# shield_passage_vitesse.net
KiCad netlist of a schematic drawn in EAGLE
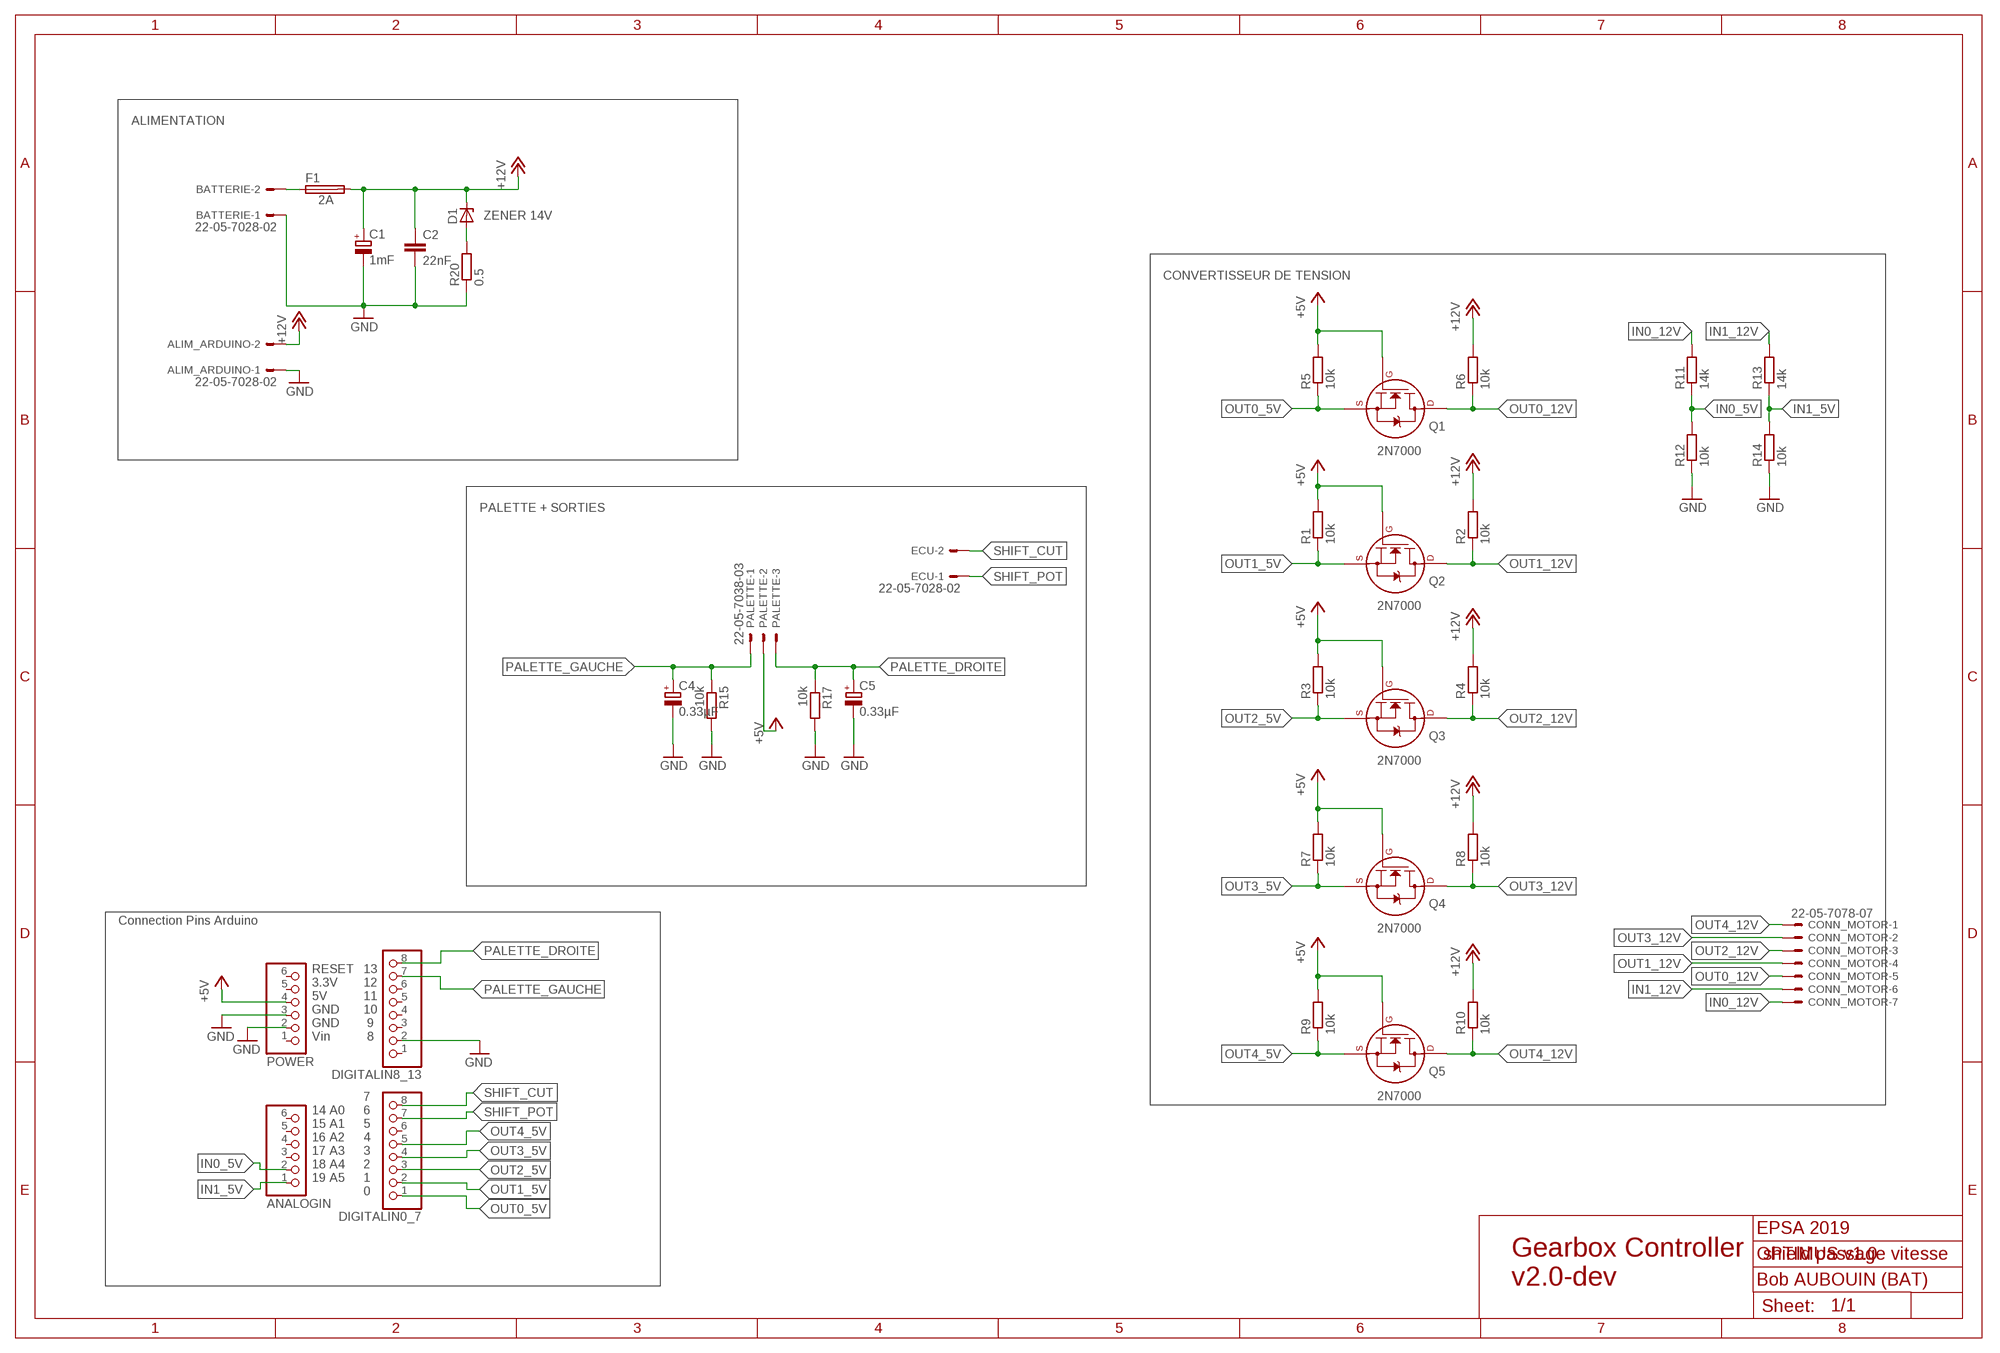
[diagram p0: schematic, sheet 1]

(export (version "E")
  (design (tool "Eeschema 10.0.6"))
  (components
    (comp (ref "ALIM_ARDUINO")
      (value "22-05-7028-02")
      (footprint "eagle-import:7395-02")
      (libsource (lib "eagle-import") (part "22-?-0205-7028"))
    )
    (comp (ref "ANALOGIN")
      (value "PINHD-1X6CB")
      (footprint "eagle-import:1X06-CLEANBIG")
      (libsource (lib "eagle-import") (part "PINHD-1X6CB"))
    )
    (comp (ref "BATTERIE")
      (value "22-05-7028-02")
      (footprint "eagle-import:7395-02")
      (libsource (lib "eagle-import") (part "22-?-0205-7028"))
    )
    (comp (ref "C1")
      (value "1mF")
      (footprint "eagle-import:E7,5-16")
      (libsource (lib "eagle-import") (part "rcl_334_CPOL-EUE7.5-16"))
    )
    (comp (ref "C2")
      (value "22nF")
      (footprint "eagle-import:C025-025X050")
      (libsource (lib "eagle-import") (part "C-EU025-025X050"))
    )
    (comp (ref "C4")
      (value "0.33µF")
      (footprint "eagle-import:E2,5-6E")
      (libsource (lib "eagle-import") (part "CPOL-EUE2,5-6E"))
    )
    (comp (ref "C5")
      (value "0.33µF")
      (footprint "eagle-import:E2,5-6E")
      (libsource (lib "eagle-import") (part "CPOL-EUE2,5-6E"))
    )
    (comp (ref "CONN_MOTOR")
      (value "22-05-7078-07")
      (footprint "eagle-import:7395-07")
      (libsource (lib "eagle-import") (part "22-?-0705-7078"))
    )
    (comp (ref "D1")
      (value "ZENER 14V")
      (footprint "eagle-import:DO41Z10")
      (libsource (lib "eagle-import") (part "ZENER-DIODEDO41Z10"))
    )
    (comp (ref "DIGITALIN0_7")
      (value "PINHD-1X8CLEANBIG")
      (footprint "eagle-import:1X08-CLEANBIG")
      (libsource (lib "eagle-import") (part "PINHD-1X8CLEANBIG"))
    )
    (comp (ref "DIGITALIN8_13")
      (value "PINHD-1X8CLEANBIG")
      (footprint "eagle-import:1X08-CLEANBIG")
      (libsource (lib "eagle-import") (part "PINHD-1X8CLEANBIG"))
    )
    (comp (ref "ECU")
      (value "22-05-7028-02")
      (footprint "eagle-import:7395-02")
      (libsource (lib "eagle-import") (part "22-?-0205-7028"))
    )
    (comp (ref "F1")
      (value "2A")
      (footprint "eagle-import:SH25")
      (fields (field (name "MF") "SCHURTER") (field (name "MPN") "0031.8211"))
      (libsource (lib "eagle-import") (part "SH25"))
    )
    (comp (ref "PALETTE")
      (value "22-05-7038-03")
      (footprint "eagle-import:7395-03")
      (libsource (lib "eagle-import") (part "22-?-0305-7038"))
    )
    (comp (ref "POWER")
      (value "PINHD-1X6CB")
      (footprint "eagle-import:1X06-CLEANBIG")
      (libsource (lib "eagle-import") (part "PINHD-1X6CB"))
    )
    (comp (ref "Q1")
      (value "2N7000")
      (footprint "eagle-import:TO-92")
      (libsource (lib "eagle-import") (part "2N700_TO920"))
    )
    (comp (ref "Q2")
      (value "2N7000")
      (footprint "eagle-import:TO-92")
      (libsource (lib "eagle-import") (part "2N700_TO920"))
    )
    (comp (ref "Q3")
      (value "2N7000")
      (footprint "eagle-import:TO-92")
      (libsource (lib "eagle-import") (part "2N700_TO920"))
    )
    (comp (ref "Q4")
      (value "2N7000")
      (footprint "eagle-import:TO-92")
      (libsource (lib "eagle-import") (part "2N700_TO920"))
    )
    (comp (ref "Q5")
      (value "2N7000")
      (footprint "eagle-import:TO-92")
      (libsource (lib "eagle-import") (part "2N700_TO920"))
    )
    (comp (ref "R1")
      (value "10k")
      (footprint "eagle-import:0204_7")
      (libsource (lib "eagle-import") (part "R-EU_0204/7"))
    )
    (comp (ref "R2")
      (value "10k")
      (footprint "eagle-import:0204_7")
      (libsource (lib "eagle-import") (part "R-EU_0204/7"))
    )
    (comp (ref "R3")
      (value "10k")
      (footprint "eagle-import:0204_7")
      (libsource (lib "eagle-import") (part "R-EU_0204/7"))
    )
    (comp (ref "R4")
      (value "10k")
      (footprint "eagle-import:0204_7")
      (libsource (lib "eagle-import") (part "R-EU_0204/7"))
    )
    (comp (ref "R5")
      (value "10k")
      (footprint "eagle-import:0204_7")
      (libsource (lib "eagle-import") (part "R-EU_0204/7"))
    )
    (comp (ref "R6")
      (value "10k")
      (footprint "eagle-import:0204_7")
      (libsource (lib "eagle-import") (part "R-EU_0204/7"))
    )
    (comp (ref "R7")
      (value "10k")
      (footprint "eagle-import:0204_7")
      (libsource (lib "eagle-import") (part "R-EU_0204/7"))
    )
    (comp (ref "R8")
      (value "10k")
      (footprint "eagle-import:0204_7")
      (libsource (lib "eagle-import") (part "R-EU_0204/7"))
    )
    (comp (ref "R9")
      (value "10k")
      (footprint "eagle-import:0204_7")
      (libsource (lib "eagle-import") (part "R-EU_0204/7"))
    )
    (comp (ref "R10")
      (value "10k")
      (footprint "eagle-import:0204_7")
      (libsource (lib "eagle-import") (part "R-EU_0204/7"))
    )
    (comp (ref "R11")
      (value "14k")
      (footprint "eagle-import:0204_7")
      (libsource (lib "eagle-import") (part "R-EU_0204/7"))
    )
    (comp (ref "R12")
      (value "10k")
      (footprint "eagle-import:0204_7")
      (libsource (lib "eagle-import") (part "R-EU_0204/7"))
    )
    (comp (ref "R13")
      (value "14k")
      (footprint "eagle-import:0204_7")
      (libsource (lib "eagle-import") (part "R-EU_0204/7"))
    )
    (comp (ref "R14")
      (value "10k")
      (footprint "eagle-import:0204_7")
      (libsource (lib "eagle-import") (part "R-EU_0204/7"))
    )
    (comp (ref "R15")
      (value "10k")
      (footprint "eagle-import:0204_7")
      (libsource (lib "eagle-import") (part "R-EU_0204/7"))
    )
    (comp (ref "R17")
      (value "10k")
      (footprint "eagle-import:0204_7")
      (libsource (lib "eagle-import") (part "R-EU_0204/7"))
    )
    (comp (ref "R20")
      (value "0.5")
      (footprint "eagle-import:0309_12")
      (libsource (lib "eagle-import") (part "R-EU_0309/12"))
    )
  )
  (nets
    (net (code "1") (name "+5V") (class "Default")
      (node (ref "PALETTE") (pin "2") (pinfunction "S_2") (pintype "passive"))
      (node (ref "POWER") (pin "4") (pinfunction "4_4") (pintype "passive"))
      (node (ref "Q1") (pin "2") (pinfunction "G_2") (pintype "tri_state"))
      (node (ref "Q2") (pin "2") (pinfunction "G_2") (pintype "tri_state"))
      (node (ref "Q3") (pin "2") (pinfunction "G_2") (pintype "tri_state"))
      (node (ref "Q4") (pin "2") (pinfunction "G_2") (pintype "tri_state"))
      (node (ref "Q5") (pin "2") (pinfunction "G_2") (pintype "tri_state"))
      (node (ref "R1") (pin "2") (pinfunction "2_2") (pintype "passive"))
      (node (ref "R3") (pin "2") (pinfunction "2_2") (pintype "passive"))
      (node (ref "R5") (pin "2") (pinfunction "2_2") (pintype "passive"))
      (node (ref "R7") (pin "2") (pinfunction "2_2") (pintype "passive"))
      (node (ref "R9") (pin "2") (pinfunction "2_2") (pintype "passive"))
    )
    (net (code "2") (name "+12V") (class "Default")
      (node (ref "ALIM_ARDUINO") (pin "2") (pinfunction "S_2") (pintype "passive"))
      (node (ref "C1") (pin "+") (pinfunction "+_+") (pintype "passive"))
      (node (ref "C2") (pin "1") (pinfunction "1_1") (pintype "passive"))
      (node (ref "D1") (pin "C") (pinfunction "C_C") (pintype "passive"))
      (node (ref "F1") (pin "2") (pinfunction "2_2") (pintype "passive"))
      (node (ref "R10") (pin "2") (pinfunction "2_2") (pintype "passive"))
      (node (ref "R2") (pin "2") (pinfunction "2_2") (pintype "passive"))
      (node (ref "R4") (pin "2") (pinfunction "2_2") (pintype "passive"))
      (node (ref "R6") (pin "2") (pinfunction "2_2") (pintype "passive"))
      (node (ref "R8") (pin "2") (pinfunction "2_2") (pintype "passive"))
    )
    (net (code "3") (name "GND") (class "Default")
      (node (ref "ALIM_ARDUINO") (pin "1") (pinfunction "S_1") (pintype "passive"))
      (node (ref "BATTERIE") (pin "1") (pinfunction "S_1") (pintype "passive"))
      (node (ref "C1") (pin "-") (pinfunction "-_-") (pintype "passive"))
      (node (ref "C2") (pin "2") (pinfunction "2_2") (pintype "passive"))
      (node (ref "C4") (pin "-") (pinfunction "-_-") (pintype "passive"))
      (node (ref "C5") (pin "-") (pinfunction "-_-") (pintype "passive"))
      (node (ref "DIGITALIN8_13") (pin "2") (pinfunction "2_2") (pintype "passive"))
      (node (ref "POWER") (pin "2") (pinfunction "2_2") (pintype "passive"))
      (node (ref "POWER") (pin "3") (pinfunction "3_3") (pintype "passive"))
      (node (ref "R12") (pin "1") (pinfunction "1_1") (pintype "passive"))
      (node (ref "R14") (pin "1") (pinfunction "1_1") (pintype "passive"))
      (node (ref "R15") (pin "2") (pinfunction "2_2") (pintype "passive"))
      (node (ref "R17") (pin "2") (pinfunction "2_2") (pintype "passive"))
      (node (ref "R20") (pin "1") (pinfunction "1_1") (pintype "passive"))
    )
    (net (code "4") (name "IN0_5V") (class "Default")
      (node (ref "ANALOGIN") (pin "2") (pinfunction "2_2") (pintype "passive"))
      (node (ref "R11") (pin "1") (pinfunction "1_1") (pintype "passive"))
      (node (ref "R12") (pin "2") (pinfunction "2_2") (pintype "passive"))
    )
    (net (code "5") (name "IN0_12V") (class "Default")
      (node (ref "CONN_MOTOR") (pin "7") (pinfunction "S_7") (pintype "passive"))
      (node (ref "R11") (pin "2") (pinfunction "2_2") (pintype "passive"))
    )
    (net (code "6") (name "IN1_5V") (class "Default")
      (node (ref "ANALOGIN") (pin "1") (pinfunction "1_1") (pintype "passive"))
      (node (ref "R13") (pin "1") (pinfunction "1_1") (pintype "passive"))
      (node (ref "R14") (pin "2") (pinfunction "2_2") (pintype "passive"))
    )
    (net (code "7") (name "IN1_12V") (class "Default")
      (node (ref "CONN_MOTOR") (pin "6") (pinfunction "S_6") (pintype "passive"))
      (node (ref "R13") (pin "2") (pinfunction "2_2") (pintype "passive"))
    )
    (net (code "8") (name "Net-(BATTERIEB-S)") (class "Default")
      (node (ref "BATTERIE") (pin "2") (pinfunction "S_2") (pintype "passive"))
      (node (ref "F1") (pin "1") (pinfunction "1_1") (pintype "passive"))
    )
    (net (code "9") (name "Net-(D1-PadA)") (class "Default")
      (node (ref "D1") (pin "A") (pinfunction "A_A") (pintype "passive"))
      (node (ref "R20") (pin "2") (pinfunction "2_2") (pintype "passive"))
    )
    (net (code "10") (name "OUT0_5V") (class "Default")
      (node (ref "DIGITALIN0_7") (pin "1") (pinfunction "1_1") (pintype "passive"))
      (node (ref "Q1") (pin "1") (pinfunction "S_1") (pintype "bidirectional"))
      (node (ref "R5") (pin "1") (pinfunction "1_1") (pintype "passive"))
    )
    (net (code "11") (name "OUT0_12V") (class "Default")
      (node (ref "CONN_MOTOR") (pin "5") (pinfunction "S_5") (pintype "passive"))
      (node (ref "Q1") (pin "3") (pinfunction "D_3") (pintype "bidirectional"))
      (node (ref "R6") (pin "1") (pinfunction "1_1") (pintype "passive"))
    )
    (net (code "12") (name "OUT1_5V") (class "Default")
      (node (ref "DIGITALIN0_7") (pin "2") (pinfunction "2_2") (pintype "passive"))
      (node (ref "Q2") (pin "1") (pinfunction "S_1") (pintype "bidirectional"))
      (node (ref "R1") (pin "1") (pinfunction "1_1") (pintype "passive"))
    )
    (net (code "13") (name "OUT1_12V") (class "Default")
      (node (ref "CONN_MOTOR") (pin "4") (pinfunction "S_4") (pintype "passive"))
      (node (ref "Q2") (pin "3") (pinfunction "D_3") (pintype "bidirectional"))
      (node (ref "R2") (pin "1") (pinfunction "1_1") (pintype "passive"))
    )
    (net (code "14") (name "OUT2_5V") (class "Default")
      (node (ref "DIGITALIN0_7") (pin "3") (pinfunction "3_3") (pintype "passive"))
      (node (ref "Q3") (pin "1") (pinfunction "S_1") (pintype "bidirectional"))
      (node (ref "R3") (pin "1") (pinfunction "1_1") (pintype "passive"))
    )
    (net (code "15") (name "OUT2_12V") (class "Default")
      (node (ref "CONN_MOTOR") (pin "3") (pinfunction "S_3") (pintype "passive"))
      (node (ref "Q3") (pin "3") (pinfunction "D_3") (pintype "bidirectional"))
      (node (ref "R4") (pin "1") (pinfunction "1_1") (pintype "passive"))
    )
    (net (code "16") (name "OUT3_5V") (class "Default")
      (node (ref "DIGITALIN0_7") (pin "4") (pinfunction "4_4") (pintype "passive"))
      (node (ref "Q4") (pin "1") (pinfunction "S_1") (pintype "bidirectional"))
      (node (ref "R7") (pin "1") (pinfunction "1_1") (pintype "passive"))
    )
    (net (code "17") (name "OUT3_12V") (class "Default")
      (node (ref "CONN_MOTOR") (pin "2") (pinfunction "S_2") (pintype "passive"))
      (node (ref "Q4") (pin "3") (pinfunction "D_3") (pintype "bidirectional"))
      (node (ref "R8") (pin "1") (pinfunction "1_1") (pintype "passive"))
    )
    (net (code "18") (name "OUT4_5V") (class "Default")
      (node (ref "DIGITALIN0_7") (pin "5") (pinfunction "5_5") (pintype "passive"))
      (node (ref "Q5") (pin "1") (pinfunction "S_1") (pintype "bidirectional"))
      (node (ref "R9") (pin "1") (pinfunction "1_1") (pintype "passive"))
    )
    (net (code "19") (name "OUT4_12V") (class "Default")
      (node (ref "CONN_MOTOR") (pin "1") (pinfunction "S_1") (pintype "passive"))
      (node (ref "Q5") (pin "3") (pinfunction "D_3") (pintype "bidirectional"))
      (node (ref "R10") (pin "1") (pinfunction "1_1") (pintype "passive"))
    )
    (net (code "20") (name "PALETTE_DROITE") (class "Default")
      (node (ref "C5") (pin "+") (pinfunction "+_+") (pintype "passive"))
      (node (ref "DIGITALIN8_13") (pin "8") (pinfunction "8_8") (pintype "passive"))
      (node (ref "PALETTE") (pin "3") (pinfunction "S_3") (pintype "passive"))
      (node (ref "R17") (pin "1") (pinfunction "1_1") (pintype "passive"))
    )
    (net (code "21") (name "PALETTE_GAUCHE") (class "Default")
      (node (ref "C4") (pin "+") (pinfunction "+_+") (pintype "passive"))
      (node (ref "DIGITALIN8_13") (pin "7") (pinfunction "7_7") (pintype "passive"))
      (node (ref "PALETTE") (pin "1") (pinfunction "S_1") (pintype "passive"))
      (node (ref "R15") (pin "1") (pinfunction "1_1") (pintype "passive"))
    )
    (net (code "22") (name "SHIFT_CUT") (class "Default")
      (node (ref "DIGITALIN0_7") (pin "8") (pinfunction "8_8") (pintype "passive"))
      (node (ref "ECU") (pin "2") (pinfunction "S_2") (pintype "passive"))
    )
    (net (code "23") (name "SHIFT_POT") (class "Default")
      (node (ref "DIGITALIN0_7") (pin "7") (pinfunction "7_7") (pintype "passive"))
      (node (ref "ECU") (pin "1") (pinfunction "S_1") (pintype "passive"))
    )
    (net (code "24") (name "unconnected-(ANALOGIN-Pad3)") (class "Default")
      (node (ref "ANALOGIN") (pin "3") (pinfunction "3_3") (pintype "passive"))
    )
    (net (code "25") (name "unconnected-(ANALOGIN-Pad4)") (class "Default")
      (node (ref "ANALOGIN") (pin "4") (pinfunction "4_4") (pintype "passive"))
    )
    (net (code "26") (name "unconnected-(ANALOGIN-Pad5)") (class "Default")
      (node (ref "ANALOGIN") (pin "5") (pinfunction "5_5") (pintype "passive"))
    )
    (net (code "27") (name "unconnected-(ANALOGIN-Pad6)") (class "Default")
      (node (ref "ANALOGIN") (pin "6") (pinfunction "6_6") (pintype "passive"))
    )
    (net (code "28") (name "unconnected-(DIGITALIN0_7-Pad6)") (class "Default")
      (node (ref "DIGITALIN0_7") (pin "6") (pinfunction "6_6") (pintype "passive"))
    )
    (net (code "29") (name "unconnected-(DIGITALIN8_13-Pad1)") (class "Default")
      (node (ref "DIGITALIN8_13") (pin "1") (pinfunction "1_1") (pintype "passive"))
    )
    (net (code "30") (name "unconnected-(DIGITALIN8_13-Pad3)") (class "Default")
      (node (ref "DIGITALIN8_13") (pin "3") (pinfunction "3_3") (pintype "passive"))
    )
    (net (code "31") (name "unconnected-(DIGITALIN8_13-Pad4)") (class "Default")
      (node (ref "DIGITALIN8_13") (pin "4") (pinfunction "4_4") (pintype "passive"))
    )
    (net (code "32") (name "unconnected-(DIGITALIN8_13-Pad5)") (class "Default")
      (node (ref "DIGITALIN8_13") (pin "5") (pinfunction "5_5") (pintype "passive"))
    )
    (net (code "33") (name "unconnected-(DIGITALIN8_13-Pad6)") (class "Default")
      (node (ref "DIGITALIN8_13") (pin "6") (pinfunction "6_6") (pintype "passive"))
    )
    (net (code "34") (name "unconnected-(POWER-Pad1)") (class "Default")
      (node (ref "POWER") (pin "1") (pinfunction "1_1") (pintype "passive"))
    )
    (net (code "35") (name "unconnected-(POWER-Pad5)") (class "Default")
      (node (ref "POWER") (pin "5") (pinfunction "5_5") (pintype "passive"))
    )
    (net (code "36") (name "unconnected-(POWER-Pad6)") (class "Default")
      (node (ref "POWER") (pin "6") (pinfunction "6_6") (pintype "passive"))
    )
  )
)
